# Top.net
KiCad netlist of a schematic drawn in Altium Designer
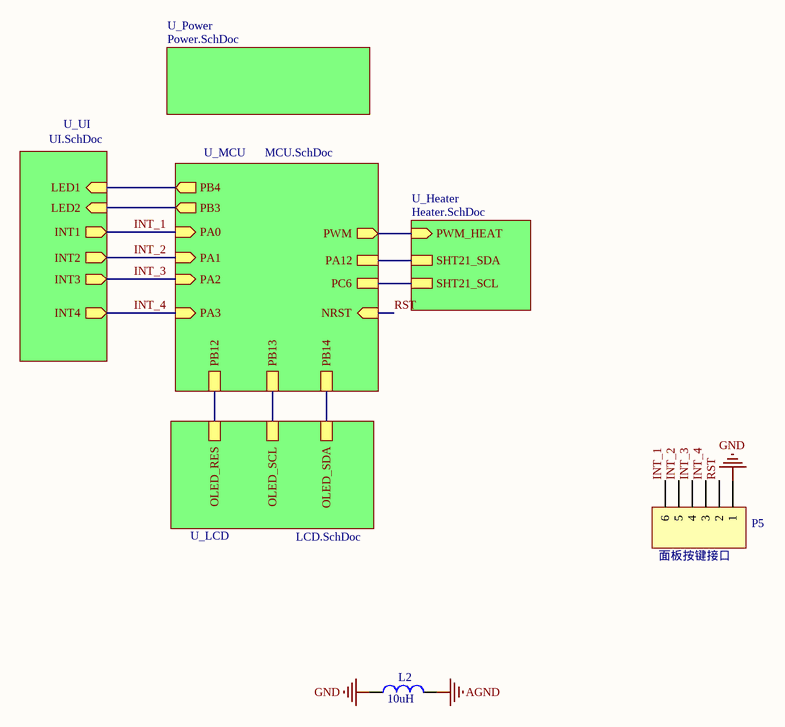
[diagram p0: Top.SchDoc]

(export (version "E")
  (design (tool "Eeschema 10.0.6"))
  (components
    (comp (ref "L2")
      (value "10uH")
      (footprint "0805")
      (fields (field (name "Comment") "Inductor"))
      (libsource (lib "原理图库") (part "Inductor"))
    )
    (comp (ref "P5")
      (value "面板按键接口")
      (footprint "软排线插座6P-0.5mm")
      (description "Header, 6-Pin")
      (fields (field (name "PUBLISHER") "Altium Limited"))
      (libsource (lib "Miscellaneous Connectors") (part "Header 6"))
    )
  )
  (nets
    (net (code "1") (name "/INT_1") (class "Default")
      (node (ref "P5") (pin "6") (pinfunction "6_6") (pintype "passive"))
    )
    (net (code "2") (name "/INT_2") (class "Default")
      (node (ref "P5") (pin "5") (pinfunction "5_5") (pintype "passive"))
    )
    (net (code "3") (name "/INT_3") (class "Default")
      (node (ref "P5") (pin "4") (pinfunction "4_4") (pintype "passive"))
    )
    (net (code "4") (name "/INT_4") (class "Default")
      (node (ref "P5") (pin "3") (pinfunction "3_3") (pintype "passive"))
    )
    (net (code "13") (name "/RST") (class "Default")
      (node (ref "P5") (pin "2") (pinfunction "2_2") (pintype "passive"))
    )
    (net (code "14") (name "AGND") (class "Default")
      (node (ref "L2") (pin "2") (pinfunction "2_2") (pintype "passive"))
    )
    (net (code "15") (name "GND") (class "Default")
      (node (ref "L2") (pin "1") (pinfunction "1_1") (pintype "passive"))
      (node (ref "P5") (pin "1") (pinfunction "1_1") (pintype "passive"))
    )
  )
)
